# Sensor_Temp.net
KiCad netlist of a schematic drawn in Altium Designer
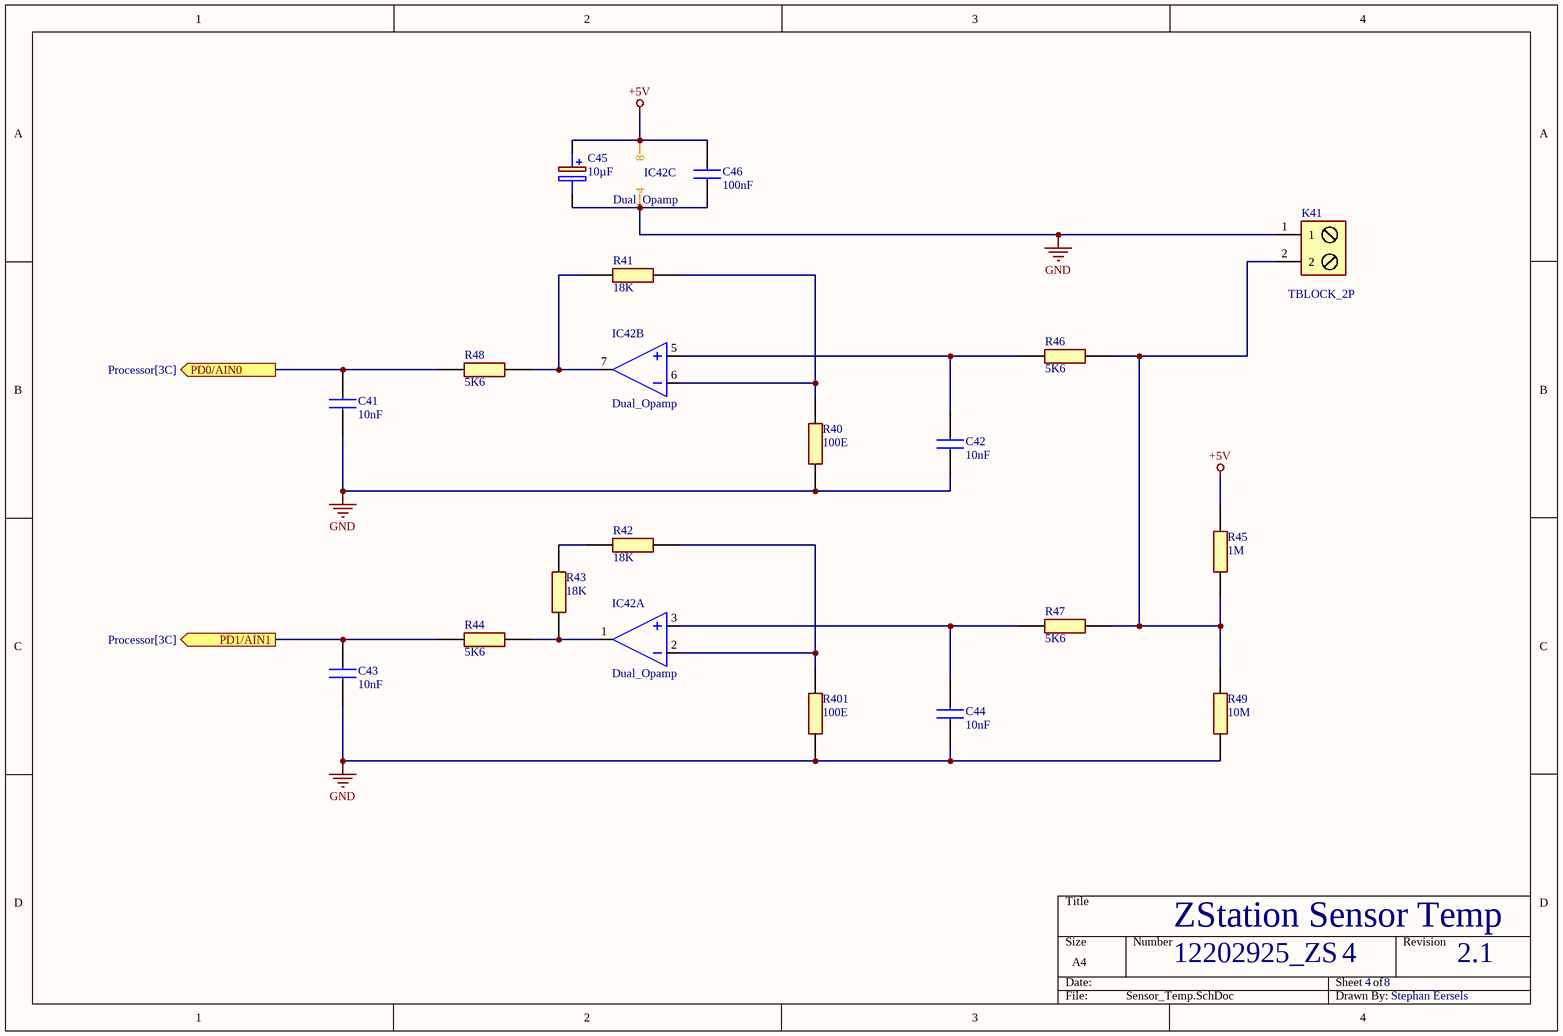
[diagram p0: Sensor_Temp.SchDoc]

(export (version "E")
  (design (tool "Eeschema 10.0.6"))
  (components
    (comp (ref "C41")
      (value "10nF")
      (footprint "C315C103K5R5TA7303")
      (fields
        (field (name "MOUSER PART NUMBER") "80-C315C103K5R-TR")
        (field (name "MANUFACTURER_PART_NUMBER") "C315C103K5R5TA7303")
      )
      (libsource (lib "Master") (part "C315C103K5R5TA7303"))
    )
    (comp (ref "C42")
      (value "10nF")
      (footprint "C315C103K5R5TA7303")
      (fields
        (field (name "MOUSER PART NUMBER") "80-C315C103K5R-TR")
        (field (name "MANUFACTURER_PART_NUMBER") "C315C103K5R5TA7303")
      )
      (libsource (lib "Master") (part "C315C103K5R5TA7303"))
    )
    (comp (ref "C43")
      (value "10nF")
      (footprint "C315C103K5R5TA7303")
      (fields
        (field (name "MOUSER PART NUMBER") "80-C315C103K5R-TR")
        (field (name "MANUFACTURER_PART_NUMBER") "C315C103K5R5TA7303")
      )
      (libsource (lib "Master") (part "C315C103K5R5TA7303"))
    )
    (comp (ref "C44")
      (value "10nF")
      (footprint "C315C103K5R5TA7303")
      (fields
        (field (name "MOUSER PART NUMBER") "80-C315C103K5R-TR")
        (field (name "MANUFACTURER_PART_NUMBER") "C315C103K5R5TA7303")
      )
      (libsource (lib "Master") (part "C315C103K5R5TA7303"))
    )
    (comp (ref "C45")
      (value "10µF")
      (footprint "Master:CAPPRD200W50D525H1250")
      (description "Aluminium Electrolytic Capacitors - Radial Leaded WCAP-AT1H 10uF 50V 20% Radial")
      (fields
        (field (name "MANUFACTURER_PART_NUMBER") "860040473003")
        (field (name "MOUSER PART NUMBER") "710-860040473003")
      )
      (libsource (lib "Master") (part "CAP_10µF_50V"))
    )
    (comp (ref "C46")
      (value "100nF")
      (footprint "Master:RDE5C1H330J0M1H03A")
      (description "CAP, 0.1UF, 50V, MLCC, RADIAL")
      (fields
        (field (name "MOUSER PART NUMBER") "81-RDER71H104K0K1H3B")
        (field (name "MANUFACTURER_PART_NUMBER") "RDER71H104K0K1H03B")
      )
      (libsource (lib "Master") (part "CAP_100nF_50V"))
    )
    (comp (ref "IC42")
      (value "Dual_Opamp")
      (footprint "Master:DIP781W56P254L950H533Q8N")
      (libsource (lib "Master") (part "Dual_Opamp"))
    )
    (comp (ref "K41")
      (value "TBLOCK_2P")
      (footprint "TBLOCK_2P")
      (description "Connector")
      (fields
        (field (name "MANUFACTURER_PART_NUMBER") "691104700002")
        (field (name "MOUSER PART NUMBER") "710-691104700002")
      )
      (libsource (lib "Master") (part "TBLOCK_2P"))
    )
    (comp (ref "R40")
      (value "100E")
      (footprint "VISHAY_CMF_60")
      (description "Through Hole 1W 10/68 Kohms 1%")
      (fields
        (field (name "MANUFACTURER_PART_NUMBER") "CMF6010K000FKEB")
        (field (name "MOUSER PART NUMBER") "71-CMF6010K000FKEB")
      )
      (libsource (lib "Master") (part "RES_68K_10K"))
    )
    (comp (ref "R41")
      (value "18K")
      (footprint "VISHAY_CMF_60")
      (description "Through Hole 1W 10/68 Kohms 1%")
      (fields
        (field (name "MANUFACTURER_PART_NUMBER") "CMF6010K000FKEB")
        (field (name "MOUSER PART NUMBER") "71-CMF6010K000FKEB")
      )
      (libsource (lib "") (part "RES_68K_10K_2"))
    )
    (comp (ref "R42")
      (value "18K")
      (footprint "VISHAY_CMF_60")
      (description "Through Hole 1W 10/68 Kohms 1%")
      (fields
        (field (name "MANUFACTURER_PART_NUMBER") "CMF6010K000FKEB")
        (field (name "MOUSER PART NUMBER") "71-CMF6010K000FKEB")
      )
      (libsource (lib "") (part "RES_68K_10K_2"))
    )
    (comp (ref "R43")
      (value "18K")
      (footprint "VISHAY_CMF_60")
      (description "Through Hole 1W 10/68 Kohms 1%")
      (fields
        (field (name "MANUFACTURER_PART_NUMBER") "CMF6010K000FKEB")
        (field (name "MOUSER PART NUMBER") "71-CMF6010K000FKEB")
      )
      (libsource (lib "") (part "RES_68K_10K_3"))
    )
    (comp (ref "R44")
      (value "5K6")
      (footprint "VISHAY_CMF_60")
      (description "Through Hole 1W 10/68 Kohms 1%")
      (fields
        (field (name "MANUFACTURER_PART_NUMBER") "CMF6010K000FKEB")
        (field (name "MOUSER PART NUMBER") "71-CMF6010K000FKEB")
      )
      (libsource (lib "") (part "RES_68K_10K_1"))
    )
    (comp (ref "R45")
      (value "1M")
      (footprint "VISHAY_CMF_60")
      (description "Through Hole 1W 10/68 Kohms 1%")
      (fields
        (field (name "MANUFACTURER_PART_NUMBER") "CMF6010K000FKEB")
        (field (name "MOUSER PART NUMBER") "71-CMF6010K000FKEB")
      )
      (libsource (lib "Master") (part "RES_68K_10K"))
    )
    (comp (ref "R46")
      (value "5K6")
      (footprint "VISHAY_CMF_60")
      (description "Through Hole 1W 10/68 Kohms 1%")
      (fields
        (field (name "MANUFACTURER_PART_NUMBER") "CMF6010K000FKEB")
        (field (name "MOUSER PART NUMBER") "71-CMF6010K000FKEB")
      )
      (libsource (lib "") (part "RES_68K_10K_1"))
    )
    (comp (ref "R47")
      (value "5K6")
      (footprint "VISHAY_CMF_60")
      (description "Through Hole 1W 10/68 Kohms 1%")
      (fields
        (field (name "MANUFACTURER_PART_NUMBER") "CMF6010K000FKEB")
        (field (name "MOUSER PART NUMBER") "71-CMF6010K000FKEB")
      )
      (libsource (lib "") (part "RES_68K_10K_1"))
    )
    (comp (ref "R48")
      (value "5K6")
      (footprint "VISHAY_CMF_60")
      (description "Through Hole 1W 10/68 Kohms 1%")
      (fields
        (field (name "MANUFACTURER_PART_NUMBER") "CMF6010K000FKEB")
        (field (name "MOUSER PART NUMBER") "71-CMF6010K000FKEB")
      )
      (libsource (lib "") (part "RES_68K_10K_1"))
    )
    (comp (ref "R49")
      (value "10M")
      (footprint "VISHAY_CMF_60")
      (description "Through Hole 1W 10/68 Kohms 1%")
      (fields
        (field (name "MANUFACTURER_PART_NUMBER") "CMF6010K000FKEB")
        (field (name "MOUSER PART NUMBER") "71-CMF6010K000FKEB")
      )
      (libsource (lib "Master") (part "RES_68K_10K"))
    )
    (comp (ref "R401")
      (value "100E")
      (footprint "VISHAY_CMF_60")
      (description "Through Hole 1W 10/68 Kohms 1%")
      (fields
        (field (name "MANUFACTURER_PART_NUMBER") "CMF6010K000FKEB")
        (field (name "MOUSER PART NUMBER") "71-CMF6010K000FKEB")
      )
      (libsource (lib "Master") (part "RES_68K_10K"))
    )
  )
  (nets
    (net (code "1") (name "+5V") (class "Default")
      (node (ref "C45") (pin "1") (pinfunction "+_1") (pintype "passive"))
      (node (ref "C46") (pin "1") (pinfunction "1_1") (pintype "passive"))
      (node (ref "IC42") (pin "8") (pinfunction "8_8") (pintype "passive"))
      (node (ref "R45") (pin "1") (pinfunction "1_1") (pintype "passive"))
    )
    (net (code "2") (name "/PD0{slash}AIN0") (class "Default")
      (node (ref "C41") (pin "2") (pinfunction "2_2") (pintype "passive"))
      (node (ref "R48") (pin "2") (pinfunction "2_2") (pintype "passive"))
    )
    (net (code "3") (name "/PD1{slash}AIN1") (class "Default")
      (node (ref "C43") (pin "2") (pinfunction "2_2") (pintype "passive"))
      (node (ref "R44") (pin "2") (pinfunction "2_2") (pintype "passive"))
    )
    (net (code "4") (name "GND") (class "Default")
      (node (ref "C41") (pin "1") (pinfunction "1_1") (pintype "passive"))
      (node (ref "C42") (pin "1") (pinfunction "1_1") (pintype "passive"))
      (node (ref "C43") (pin "1") (pinfunction "1_1") (pintype "passive"))
      (node (ref "C44") (pin "1") (pinfunction "1_1") (pintype "passive"))
      (node (ref "C45") (pin "2") (pinfunction "-_2") (pintype "passive"))
      (node (ref "C46") (pin "2") (pinfunction "2_2") (pintype "passive"))
      (node (ref "IC42") (pin "4") (pinfunction "4_4") (pintype "passive"))
      (node (ref "K41") (pin "1") (pinfunction "1_1") (pintype "passive"))
      (node (ref "R40") (pin "2") (pinfunction "2_2") (pintype "passive"))
      (node (ref "R401") (pin "2") (pinfunction "2_2") (pintype "passive"))
      (node (ref "R49") (pin "2") (pinfunction "2_2") (pintype "passive"))
    )
    (net (code "5") (name "Net-(IC42A-VINA+)") (class "Default")
      (node (ref "C44") (pin "2") (pinfunction "2_2") (pintype "passive"))
      (node (ref "IC42") (pin "3") (pinfunction "VINA+_3") (pintype "passive"))
      (node (ref "R47") (pin "2") (pinfunction "2_2") (pintype "passive"))
    )
    (net (code "6") (name "Net-(IC42A-VINA-)") (class "Default")
      (node (ref "IC42") (pin "2") (pinfunction "VINA-_2") (pintype "passive"))
      (node (ref "R401") (pin "1") (pinfunction "1_1") (pintype "passive"))
      (node (ref "R42") (pin "2") (pinfunction "2_2") (pintype "passive"))
    )
    (net (code "7") (name "Net-(IC42A-VOUTA)") (class "Default")
      (node (ref "IC42") (pin "1") (pinfunction "VOUTA_1") (pintype "passive"))
      (node (ref "R43") (pin "1") (pinfunction "1_1") (pintype "passive"))
      (node (ref "R44") (pin "1") (pinfunction "1_1") (pintype "passive"))
    )
    (net (code "8") (name "Net-(IC42B-VINB+)") (class "Default")
      (node (ref "C42") (pin "2") (pinfunction "2_2") (pintype "passive"))
      (node (ref "IC42") (pin "5") (pinfunction "VINB+_5") (pintype "passive"))
      (node (ref "R46") (pin "2") (pinfunction "2_2") (pintype "passive"))
    )
    (net (code "9") (name "Net-(IC42B-VINB-)") (class "Default")
      (node (ref "IC42") (pin "6") (pinfunction "VINB-_6") (pintype "passive"))
      (node (ref "R40") (pin "1") (pinfunction "1_1") (pintype "passive"))
      (node (ref "R41") (pin "2") (pinfunction "2_2") (pintype "passive"))
    )
    (net (code "10") (name "Net-(IC42B-VOUTB)") (class "Default")
      (node (ref "IC42") (pin "7") (pinfunction "VOUTB_7") (pintype "passive"))
      (node (ref "R41") (pin "1") (pinfunction "1_1") (pintype "passive"))
      (node (ref "R48") (pin "1") (pinfunction "1_1") (pintype "passive"))
    )
    (net (code "11") (name "Net-(K41-Pad2)") (class "Default")
      (node (ref "K41") (pin "2") (pinfunction "2_2") (pintype "passive"))
      (node (ref "R45") (pin "2") (pinfunction "2_2") (pintype "passive"))
      (node (ref "R46") (pin "1") (pinfunction "1_1") (pintype "passive"))
      (node (ref "R47") (pin "1") (pinfunction "1_1") (pintype "passive"))
      (node (ref "R49") (pin "1") (pinfunction "1_1") (pintype "passive"))
    )
    (net (code "12") (name "Net-(R42-Pad1)") (class "Default")
      (node (ref "R42") (pin "1") (pinfunction "1_1") (pintype "passive"))
      (node (ref "R43") (pin "2") (pinfunction "2_2") (pintype "passive"))
    )
  )
)
